# Battery.net
KiCad netlist of a schematic drawn in Altium Designer
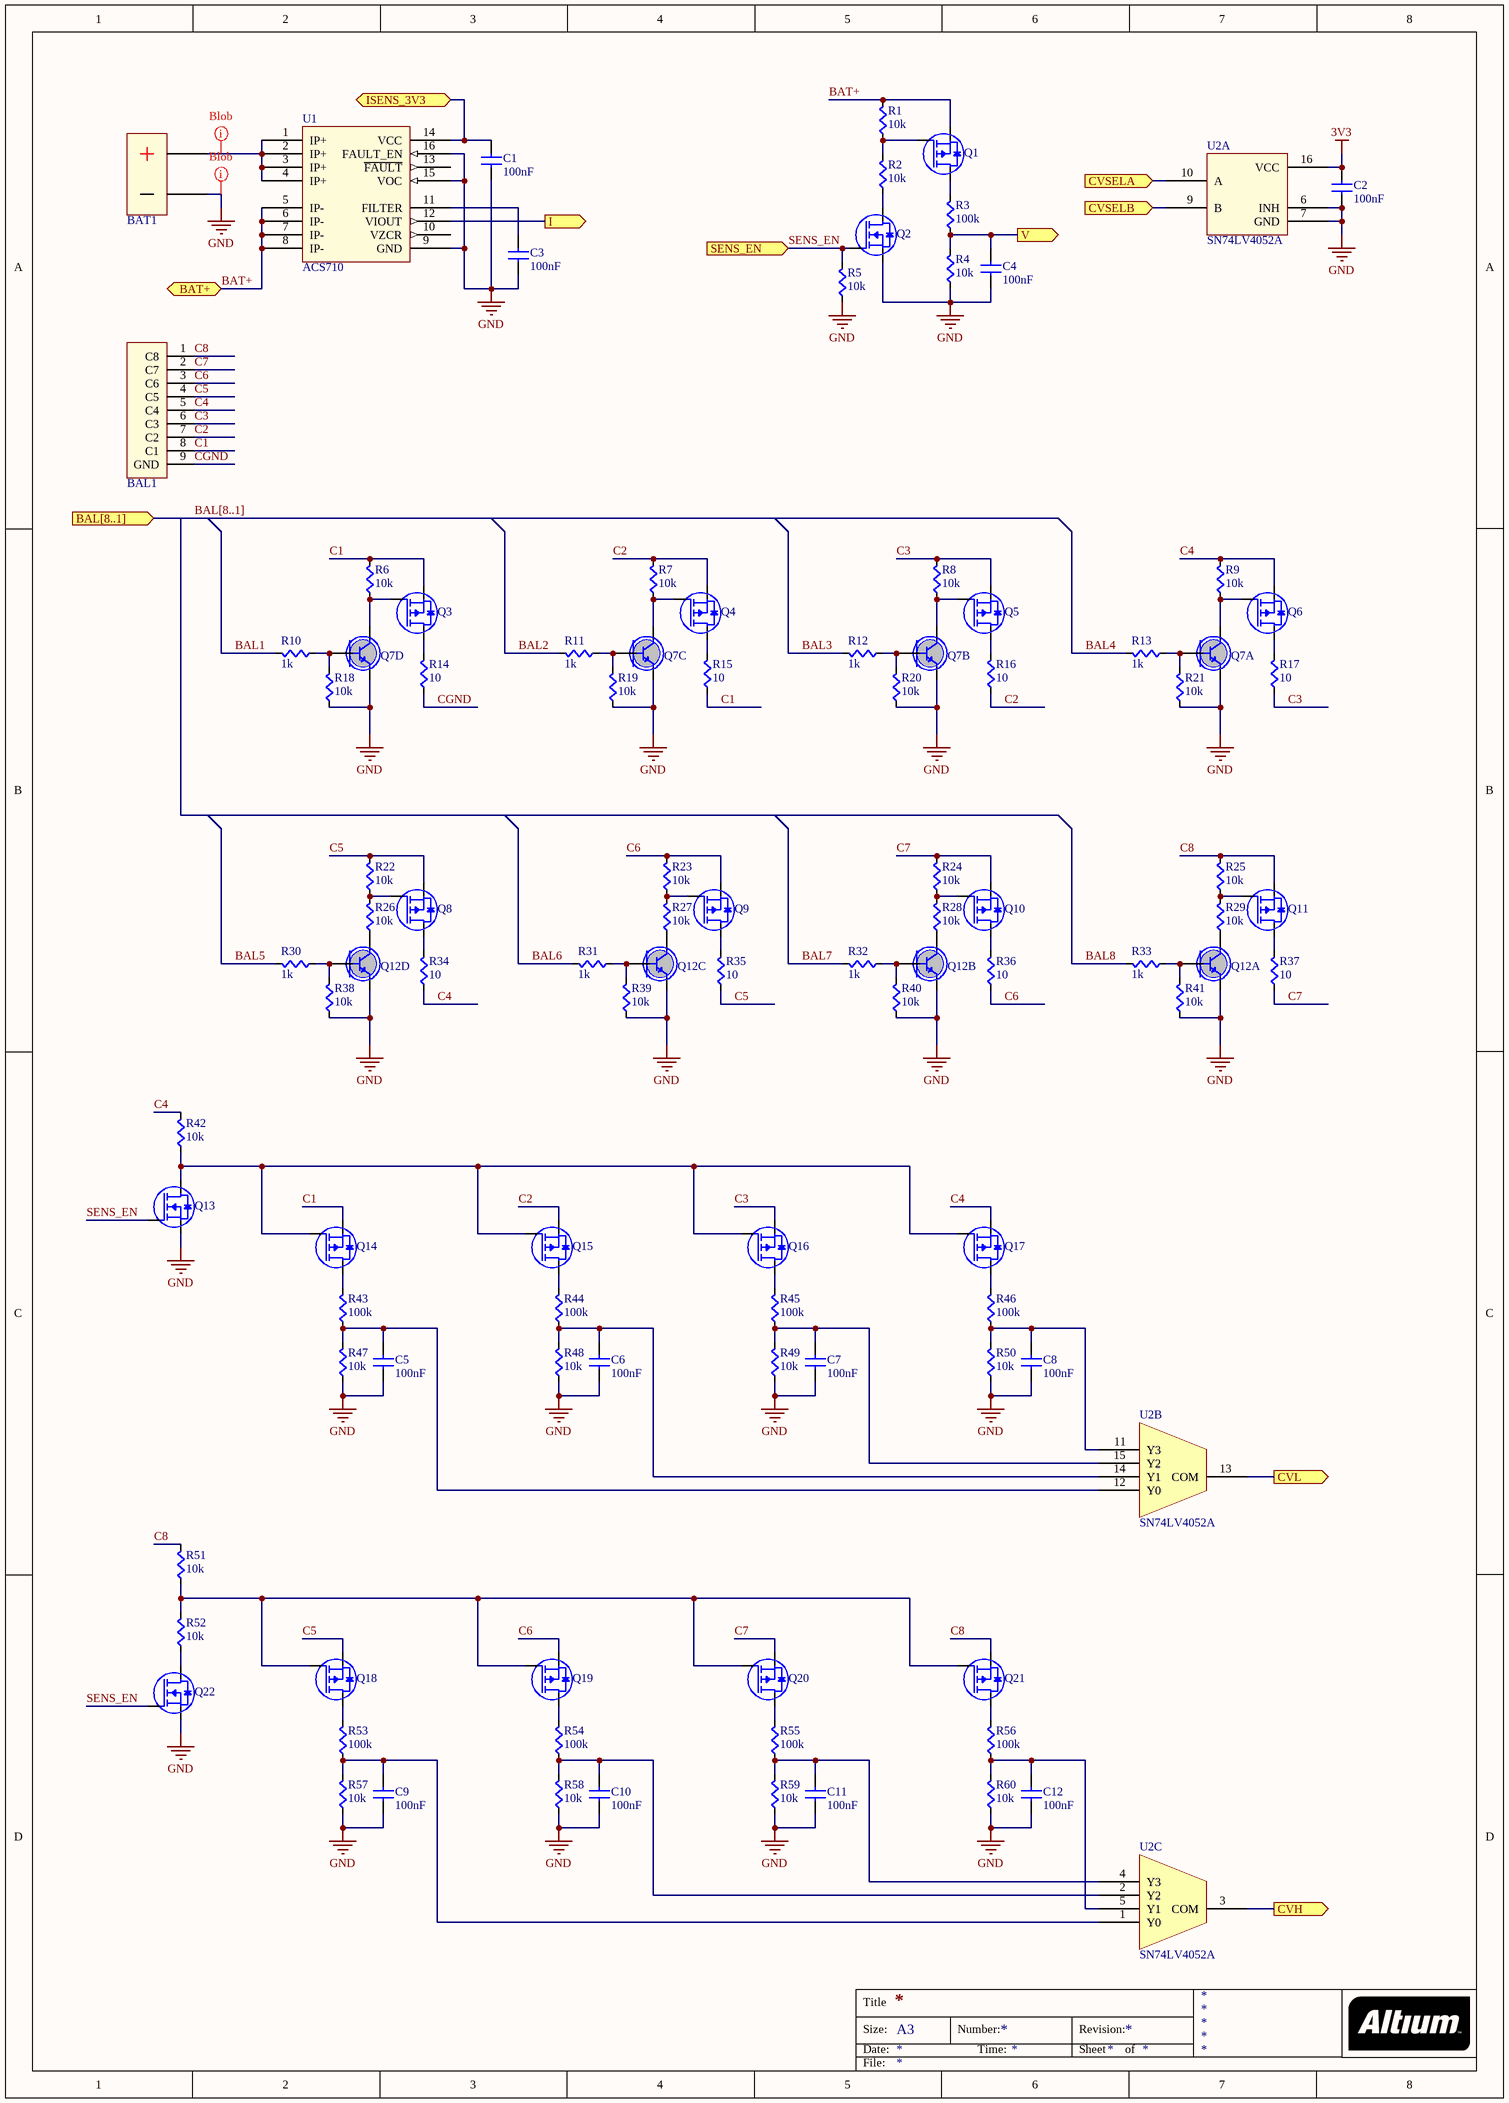
[diagram p0: Battery.SchDoc]

(export (version "E")
  (design (tool "Eeschema 10.0.6"))
  (components
    (comp (ref "BAL1") (value "JST1x9") (footprint "JST1x9") (libsource (lib "SubjuGator8") (part "JST1x9")))
    (comp (ref "BAT1")
      (value "BATWIRE")
      (footprint "BATWIRE12")
      (description "Two large gauge leads soldered directly to the board.")
      (libsource (lib "SubjuGator8") (part "BATWIRE"))
    )
    (comp (ref "C1")
      (value "100nF")
      (footprint "CAPC0603")
      (fields (field (name "Comment") "Cap"))
      (libsource (lib "SubjuGator8") (part "Cap"))
    )
    (comp (ref "C2")
      (value "100nF")
      (footprint "CAPC0603")
      (fields (field (name "Comment") "Cap"))
      (libsource (lib "SubjuGator8") (part "Cap"))
    )
    (comp (ref "C3")
      (value "100nF")
      (footprint "CAPC0603")
      (fields (field (name "Comment") "Cap"))
      (libsource (lib "SubjuGator8") (part "Cap"))
    )
    (comp (ref "C4")
      (value "100nF")
      (footprint "CAPC0603")
      (fields (field (name "Comment") "Cap"))
      (libsource (lib "SubjuGator8") (part "Cap"))
    )
    (comp (ref "C5")
      (value "100nF")
      (footprint "CAPC0603")
      (fields (field (name "Comment") "Cap"))
      (libsource (lib "SubjuGator8") (part "Cap"))
    )
    (comp (ref "C6")
      (value "100nF")
      (footprint "CAPC0603")
      (fields (field (name "Comment") "Cap"))
      (libsource (lib "SubjuGator8") (part "Cap"))
    )
    (comp (ref "C7")
      (value "100nF")
      (footprint "CAPC0603")
      (fields (field (name "Comment") "Cap"))
      (libsource (lib "SubjuGator8") (part "Cap"))
    )
    (comp (ref "C8")
      (value "100nF")
      (footprint "CAPC0603")
      (fields (field (name "Comment") "Cap"))
      (libsource (lib "SubjuGator8") (part "Cap"))
    )
    (comp (ref "C9")
      (value "100nF")
      (footprint "CAPC0603")
      (fields (field (name "Comment") "Cap"))
      (libsource (lib "SubjuGator8") (part "Cap"))
    )
    (comp (ref "C10")
      (value "100nF")
      (footprint "CAPC0603")
      (fields (field (name "Comment") "Cap"))
      (libsource (lib "SubjuGator8") (part "Cap"))
    )
    (comp (ref "C11")
      (value "100nF")
      (footprint "CAPC0603")
      (fields (field (name "Comment") "Cap"))
      (libsource (lib "SubjuGator8") (part "Cap"))
    )
    (comp (ref "C12")
      (value "100nF")
      (footprint "CAPC0603")
      (fields (field (name "Comment") "Cap"))
      (libsource (lib "SubjuGator8") (part "Cap"))
    )
    (comp (ref "Q1")
      (value "FDN5618P")
      (footprint "PowerSOT-3")
      (description "60V P-Channel Logic Level PowerTrench MOSFET")
      (libsource (lib "SubjuGator8") (part "FDN5618P"))
    )
    (comp (ref "Q2")
      (value "FDN5630")
      (footprint "PowerSOT-3")
      (description "60V N-Channel PowerTrench MOSFET")
      (libsource (lib "SubjuGator8") (part "FDN5630"))
    )
    (comp (ref "Q3")
      (value "FDN5618P")
      (footprint "PowerSOT-3")
      (description "60V P-Channel Logic Level PowerTrench MOSFET")
      (libsource (lib "SubjuGator8") (part "FDN5618P"))
    )
    (comp (ref "Q4")
      (value "FDN5618P")
      (footprint "PowerSOT-3")
      (description "60V P-Channel Logic Level PowerTrench MOSFET")
      (libsource (lib "SubjuGator8") (part "FDN5618P"))
    )
    (comp (ref "Q5")
      (value "FDN5618P")
      (footprint "PowerSOT-3")
      (description "60V P-Channel Logic Level PowerTrench MOSFET")
      (libsource (lib "SubjuGator8") (part "FDN5618P"))
    )
    (comp (ref "Q6")
      (value "FDN5618P")
      (footprint "PowerSOT-3")
      (description "60V P-Channel Logic Level PowerTrench MOSFET")
      (libsource (lib "SubjuGator8") (part "FDN5618P"))
    )
    (comp (ref "Q7")
      (value "MMPQ2222A")
      (footprint "MMPQ2222A")
      (description "Quad NPN General Purpose Amplifier")
      (libsource (lib "SubjuGator8") (part "MMPQ2222A"))
    )
    (comp (ref "Q8")
      (value "FDN5618P")
      (footprint "PowerSOT-3")
      (description "60V P-Channel Logic Level PowerTrench MOSFET")
      (libsource (lib "SubjuGator8") (part "FDN5618P"))
    )
    (comp (ref "Q9")
      (value "FDN5618P")
      (footprint "PowerSOT-3")
      (description "60V P-Channel Logic Level PowerTrench MOSFET")
      (libsource (lib "SubjuGator8") (part "FDN5618P"))
    )
    (comp (ref "Q10")
      (value "FDN5618P")
      (footprint "PowerSOT-3")
      (description "60V P-Channel Logic Level PowerTrench MOSFET")
      (libsource (lib "SubjuGator8") (part "FDN5618P"))
    )
    (comp (ref "Q11")
      (value "FDN5618P")
      (footprint "PowerSOT-3")
      (description "60V P-Channel Logic Level PowerTrench MOSFET")
      (libsource (lib "SubjuGator8") (part "FDN5618P"))
    )
    (comp (ref "Q12")
      (value "MMPQ2222A")
      (footprint "MMPQ2222A")
      (description "Quad NPN General Purpose Amplifier")
      (libsource (lib "SubjuGator8") (part "MMPQ2222A"))
    )
    (comp (ref "Q13")
      (value "FDN5630")
      (footprint "PowerSOT-3")
      (description "60V N-Channel PowerTrench MOSFET")
      (libsource (lib "SubjuGator8") (part "FDN5630"))
    )
    (comp (ref "Q14")
      (value "FDN5618P")
      (footprint "PowerSOT-3")
      (description "60V P-Channel Logic Level PowerTrench MOSFET")
      (libsource (lib "SubjuGator8") (part "FDN5618P"))
    )
    (comp (ref "Q15")
      (value "FDN5618P")
      (footprint "PowerSOT-3")
      (description "60V P-Channel Logic Level PowerTrench MOSFET")
      (libsource (lib "SubjuGator8") (part "FDN5618P"))
    )
    (comp (ref "Q16")
      (value "FDN5618P")
      (footprint "PowerSOT-3")
      (description "60V P-Channel Logic Level PowerTrench MOSFET")
      (libsource (lib "SubjuGator8") (part "FDN5618P"))
    )
    (comp (ref "Q17")
      (value "FDN5618P")
      (footprint "PowerSOT-3")
      (description "60V P-Channel Logic Level PowerTrench MOSFET")
      (libsource (lib "SubjuGator8") (part "FDN5618P"))
    )
    (comp (ref "Q18")
      (value "FDN5618P")
      (footprint "PowerSOT-3")
      (description "60V P-Channel Logic Level PowerTrench MOSFET")
      (libsource (lib "SubjuGator8") (part "FDN5618P"))
    )
    (comp (ref "Q19")
      (value "FDN5618P")
      (footprint "PowerSOT-3")
      (description "60V P-Channel Logic Level PowerTrench MOSFET")
      (libsource (lib "SubjuGator8") (part "FDN5618P"))
    )
    (comp (ref "Q20")
      (value "FDN5618P")
      (footprint "PowerSOT-3")
      (description "60V P-Channel Logic Level PowerTrench MOSFET")
      (libsource (lib "SubjuGator8") (part "FDN5618P"))
    )
    (comp (ref "Q21")
      (value "FDN5618P")
      (footprint "PowerSOT-3")
      (description "60V P-Channel Logic Level PowerTrench MOSFET")
      (libsource (lib "SubjuGator8") (part "FDN5618P"))
    )
    (comp (ref "Q22")
      (value "FDN5630")
      (footprint "PowerSOT-3")
      (description "60V N-Channel PowerTrench MOSFET")
      (libsource (lib "SubjuGator8") (part "FDN5630"))
    )
    (comp (ref "R1")
      (value "10k")
      (footprint "RES0603")
      (fields (field (name "Comment") "Res"))
      (libsource (lib "SubjuGator8") (part "Res"))
    )
    (comp (ref "R2")
      (value "10k")
      (footprint "RES0603")
      (fields (field (name "Comment") "Res"))
      (libsource (lib "SubjuGator8") (part "Res"))
    )
    (comp (ref "R3")
      (value "100k")
      (footprint "RES0603")
      (fields (field (name "Comment") "Res"))
      (libsource (lib "SubjuGator8") (part "Res"))
    )
    (comp (ref "R4")
      (value "10k")
      (footprint "RES0603")
      (fields (field (name "Comment") "Res"))
      (libsource (lib "SubjuGator8") (part "Res"))
    )
    (comp (ref "R5")
      (value "10k")
      (footprint "RES0603")
      (fields (field (name "Comment") "Res"))
      (libsource (lib "SubjuGator8") (part "Res"))
    )
    (comp (ref "R6")
      (value "10k")
      (footprint "RES0603")
      (fields (field (name "Comment") "Res"))
      (libsource (lib "SubjuGator8") (part "Res"))
    )
    (comp (ref "R7")
      (value "10k")
      (footprint "RES0603")
      (fields (field (name "Comment") "Res"))
      (libsource (lib "SubjuGator8") (part "Res"))
    )
    (comp (ref "R8")
      (value "10k")
      (footprint "RES0603")
      (fields (field (name "Comment") "Res"))
      (libsource (lib "SubjuGator8") (part "Res"))
    )
    (comp (ref "R9")
      (value "10k")
      (footprint "RES0603")
      (fields (field (name "Comment") "Res"))
      (libsource (lib "SubjuGator8") (part "Res"))
    )
    (comp (ref "R10")
      (value "1k")
      (footprint "RES0603")
      (fields (field (name "Comment") "Res"))
      (libsource (lib "SubjuGator8") (part "Res"))
    )
    (comp (ref "R11")
      (value "1k")
      (footprint "RES0603")
      (fields (field (name "Comment") "Res"))
      (libsource (lib "SubjuGator8") (part "Res"))
    )
    (comp (ref "R12")
      (value "1k")
      (footprint "RES0603")
      (fields (field (name "Comment") "Res"))
      (libsource (lib "SubjuGator8") (part "Res"))
    )
    (comp (ref "R13")
      (value "1k")
      (footprint "RES0603")
      (fields (field (name "Comment") "Res"))
      (libsource (lib "SubjuGator8") (part "Res"))
    )
    (comp (ref "R14")
      (value "10")
      (footprint "FMP200")
      (fields (field (name "Comment") "Res"))
      (libsource (lib "SubjuGator8") (part "Res"))
    )
    (comp (ref "R15")
      (value "10")
      (footprint "FMP200")
      (fields (field (name "Comment") "Res"))
      (libsource (lib "SubjuGator8") (part "Res"))
    )
    (comp (ref "R16")
      (value "10")
      (footprint "FMP200")
      (fields (field (name "Comment") "Res"))
      (libsource (lib "SubjuGator8") (part "Res"))
    )
    (comp (ref "R17")
      (value "10")
      (footprint "FMP200")
      (fields (field (name "Comment") "Res"))
      (libsource (lib "SubjuGator8") (part "Res"))
    )
    (comp (ref "R18")
      (value "10k")
      (footprint "RES0603")
      (fields (field (name "Comment") "Res"))
      (libsource (lib "SubjuGator8") (part "Res"))
    )
    (comp (ref "R19")
      (value "10k")
      (footprint "RES0603")
      (fields (field (name "Comment") "Res"))
      (libsource (lib "SubjuGator8") (part "Res"))
    )
    (comp (ref "R20")
      (value "10k")
      (footprint "RES0603")
      (fields (field (name "Comment") "Res"))
      (libsource (lib "SubjuGator8") (part "Res"))
    )
    (comp (ref "R21")
      (value "10k")
      (footprint "RES0603")
      (fields (field (name "Comment") "Res"))
      (libsource (lib "SubjuGator8") (part "Res"))
    )
    (comp (ref "R22")
      (value "10k")
      (footprint "RES0603")
      (fields (field (name "Comment") "Res"))
      (libsource (lib "SubjuGator8") (part "Res"))
    )
    (comp (ref "R23")
      (value "10k")
      (footprint "RES0603")
      (fields (field (name "Comment") "Res"))
      (libsource (lib "SubjuGator8") (part "Res"))
    )
    (comp (ref "R24")
      (value "10k")
      (footprint "RES0603")
      (fields (field (name "Comment") "Res"))
      (libsource (lib "SubjuGator8") (part "Res"))
    )
    (comp (ref "R25")
      (value "10k")
      (footprint "RES0603")
      (fields (field (name "Comment") "Res"))
      (libsource (lib "SubjuGator8") (part "Res"))
    )
    (comp (ref "R26")
      (value "10k")
      (footprint "RES0603")
      (fields (field (name "Comment") "Res"))
      (libsource (lib "SubjuGator8") (part "Res"))
    )
    (comp (ref "R27")
      (value "10k")
      (footprint "RES0603")
      (fields (field (name "Comment") "Res"))
      (libsource (lib "SubjuGator8") (part "Res"))
    )
    (comp (ref "R28")
      (value "10k")
      (footprint "RES0603")
      (fields (field (name "Comment") "Res"))
      (libsource (lib "SubjuGator8") (part "Res"))
    )
    (comp (ref "R29")
      (value "10k")
      (footprint "RES0603")
      (fields (field (name "Comment") "Res"))
      (libsource (lib "SubjuGator8") (part "Res"))
    )
    (comp (ref "R30")
      (value "1k")
      (footprint "RES0603")
      (fields (field (name "Comment") "Res"))
      (libsource (lib "SubjuGator8") (part "Res"))
    )
    (comp (ref "R31")
      (value "1k")
      (footprint "RES0603")
      (fields (field (name "Comment") "Res"))
      (libsource (lib "SubjuGator8") (part "Res"))
    )
    (comp (ref "R32")
      (value "1k")
      (footprint "RES0603")
      (fields (field (name "Comment") "Res"))
      (libsource (lib "SubjuGator8") (part "Res"))
    )
    (comp (ref "R33")
      (value "1k")
      (footprint "RES0603")
      (fields (field (name "Comment") "Res"))
      (libsource (lib "SubjuGator8") (part "Res"))
    )
    (comp (ref "R34")
      (value "10")
      (footprint "FMP200")
      (fields (field (name "Comment") "Res"))
      (libsource (lib "SubjuGator8") (part "Res"))
    )
    (comp (ref "R35")
      (value "10")
      (footprint "FMP200")
      (fields (field (name "Comment") "Res"))
      (libsource (lib "SubjuGator8") (part "Res"))
    )
    (comp (ref "R36")
      (value "10")
      (footprint "FMP200")
      (fields (field (name "Comment") "Res"))
      (libsource (lib "SubjuGator8") (part "Res"))
    )
    (comp (ref "R37")
      (value "10")
      (footprint "FMP200")
      (fields (field (name "Comment") "Res"))
      (libsource (lib "SubjuGator8") (part "Res"))
    )
    (comp (ref "R38")
      (value "10k")
      (footprint "RES0603")
      (fields (field (name "Comment") "Res"))
      (libsource (lib "SubjuGator8") (part "Res"))
    )
    (comp (ref "R39")
      (value "10k")
      (footprint "RES0603")
      (fields (field (name "Comment") "Res"))
      (libsource (lib "SubjuGator8") (part "Res"))
    )
    (comp (ref "R40")
      (value "10k")
      (footprint "RES0603")
      (fields (field (name "Comment") "Res"))
      (libsource (lib "SubjuGator8") (part "Res"))
    )
    (comp (ref "R41")
      (value "10k")
      (footprint "RES0603")
      (fields (field (name "Comment") "Res"))
      (libsource (lib "SubjuGator8") (part "Res"))
    )
    (comp (ref "R42")
      (value "10k")
      (footprint "RES0603")
      (fields (field (name "Comment") "Res"))
      (libsource (lib "SubjuGator8") (part "Res"))
    )
    (comp (ref "R43")
      (value "100k")
      (footprint "RES0603")
      (fields (field (name "Comment") "Res"))
      (libsource (lib "SubjuGator8") (part "Res"))
    )
    (comp (ref "R44")
      (value "100k")
      (footprint "RES0603")
      (fields (field (name "Comment") "Res"))
      (libsource (lib "SubjuGator8") (part "Res"))
    )
    (comp (ref "R45")
      (value "100k")
      (footprint "RES0603")
      (fields (field (name "Comment") "Res"))
      (libsource (lib "SubjuGator8") (part "Res"))
    )
    (comp (ref "R46")
      (value "100k")
      (footprint "RES0603")
      (fields (field (name "Comment") "Res"))
      (libsource (lib "SubjuGator8") (part "Res"))
    )
    (comp (ref "R47")
      (value "10k")
      (footprint "RES0603")
      (fields (field (name "Comment") "Res"))
      (libsource (lib "SubjuGator8") (part "Res"))
    )
    (comp (ref "R48")
      (value "10k")
      (footprint "RES0603")
      (fields (field (name "Comment") "Res"))
      (libsource (lib "SubjuGator8") (part "Res"))
    )
    (comp (ref "R49")
      (value "10k")
      (footprint "RES0603")
      (fields (field (name "Comment") "Res"))
      (libsource (lib "SubjuGator8") (part "Res"))
    )
    (comp (ref "R50")
      (value "10k")
      (footprint "RES0603")
      (fields (field (name "Comment") "Res"))
      (libsource (lib "SubjuGator8") (part "Res"))
    )
    (comp (ref "R51")
      (value "10k")
      (footprint "RES0603")
      (fields (field (name "Comment") "Res"))
      (libsource (lib "SubjuGator8") (part "Res"))
    )
    (comp (ref "R52")
      (value "10k")
      (footprint "RES0603")
      (fields (field (name "Comment") "Res"))
      (libsource (lib "SubjuGator8") (part "Res"))
    )
    (comp (ref "R53")
      (value "100k")
      (footprint "RES0603")
      (fields (field (name "Comment") "Res"))
      (libsource (lib "SubjuGator8") (part "Res"))
    )
    (comp (ref "R54")
      (value "100k")
      (footprint "RES0603")
      (fields (field (name "Comment") "Res"))
      (libsource (lib "SubjuGator8") (part "Res"))
    )
    (comp (ref "R55")
      (value "100k")
      (footprint "RES0603")
      (fields (field (name "Comment") "Res"))
      (libsource (lib "SubjuGator8") (part "Res"))
    )
    (comp (ref "R56")
      (value "100k")
      (footprint "RES0603")
      (fields (field (name "Comment") "Res"))
      (libsource (lib "SubjuGator8") (part "Res"))
    )
    (comp (ref "R57")
      (value "10k")
      (footprint "RES0603")
      (fields (field (name "Comment") "Res"))
      (libsource (lib "SubjuGator8") (part "Res"))
    )
    (comp (ref "R58")
      (value "10k")
      (footprint "RES0603")
      (fields (field (name "Comment") "Res"))
      (libsource (lib "SubjuGator8") (part "Res"))
    )
    (comp (ref "R59")
      (value "10k")
      (footprint "RES0603")
      (fields (field (name "Comment") "Res"))
      (libsource (lib "SubjuGator8") (part "Res"))
    )
    (comp (ref "R60")
      (value "10k")
      (footprint "RES0603")
      (fields (field (name "Comment") "Res"))
      (libsource (lib "SubjuGator8") (part "Res"))
    )
    (comp (ref "U1")
      (value "ACS710")
      (footprint "ACS710_NOPIN")
      (description "Current Sensor with Integrated Overcurrent Detection")
      (libsource (lib "SubjuGator8") (part "ACS710"))
    )
    (comp (ref "U2")
      (value "SN74LV4052A")
      (footprint "SN74LV4052AD")
      (description "Dual 4-Channel Analog Multiplexers/Demultiplexers")
      (libsource (lib "SubjuGator8") (part "SN74LV4052A"))
    )
  )
  (nets
    (net (code "1") (name "/BAL1") (class "Default")
      (node (ref "R10") (pin "1") (pinfunction "A_1") (pintype "passive"))
    )
    (net (code "2") (name "/BAL2") (class "Default")
      (node (ref "R11") (pin "1") (pinfunction "A_1") (pintype "passive"))
    )
    (net (code "3") (name "/BAL3") (class "Default")
      (node (ref "R12") (pin "1") (pinfunction "A_1") (pintype "passive"))
    )
    (net (code "4") (name "/BAL4") (class "Default")
      (node (ref "R13") (pin "1") (pinfunction "A_1") (pintype "passive"))
    )
    (net (code "5") (name "/BAL5") (class "Default")
      (node (ref "R30") (pin "1") (pinfunction "A_1") (pintype "passive"))
    )
    (net (code "6") (name "/BAL6") (class "Default")
      (node (ref "R31") (pin "1") (pinfunction "A_1") (pintype "passive"))
    )
    (net (code "7") (name "/BAL7") (class "Default")
      (node (ref "R32") (pin "1") (pinfunction "A_1") (pintype "passive"))
    )
    (net (code "8") (name "/BAL8") (class "Default")
      (node (ref "R33") (pin "1") (pinfunction "A_1") (pintype "passive"))
    )
    (net (code "10") (name "/BAT+") (class "Default")
      (node (ref "Q1") (pin "S") (pinfunction "S_S") (pintype "passive"))
      (node (ref "R1") (pin "1") (pinfunction "A_1") (pintype "passive"))
      (node (ref "U1") (pin "5") (pinfunction "IP-_5") (pintype "passive"))
      (node (ref "U1") (pin "6") (pinfunction "IP-_6") (pintype "passive"))
      (node (ref "U1") (pin "7") (pinfunction "IP-_7") (pintype "passive"))
      (node (ref "U1") (pin "8") (pinfunction "IP-_8") (pintype "passive"))
    )
    (net (code "11") (name "/C1") (class "Default")
      (node (ref "BAL1") (pin "8") (pinfunction "C1_8") (pintype "passive"))
      (node (ref "Q14") (pin "S") (pinfunction "S_S") (pintype "passive"))
      (node (ref "Q3") (pin "S") (pinfunction "S_S") (pintype "passive"))
      (node (ref "R15") (pin "2") (pinfunction "B_2") (pintype "passive"))
      (node (ref "R6") (pin "1") (pinfunction "A_1") (pintype "passive"))
    )
    (net (code "12") (name "/C2") (class "Default")
      (node (ref "BAL1") (pin "7") (pinfunction "C2_7") (pintype "passive"))
      (node (ref "Q15") (pin "S") (pinfunction "S_S") (pintype "passive"))
      (node (ref "Q4") (pin "S") (pinfunction "S_S") (pintype "passive"))
      (node (ref "R16") (pin "2") (pinfunction "B_2") (pintype "passive"))
      (node (ref "R7") (pin "1") (pinfunction "A_1") (pintype "passive"))
    )
    (net (code "13") (name "/C3") (class "Default")
      (node (ref "BAL1") (pin "6") (pinfunction "C3_6") (pintype "passive"))
      (node (ref "Q16") (pin "S") (pinfunction "S_S") (pintype "passive"))
      (node (ref "Q5") (pin "S") (pinfunction "S_S") (pintype "passive"))
      (node (ref "R17") (pin "2") (pinfunction "B_2") (pintype "passive"))
      (node (ref "R8") (pin "1") (pinfunction "A_1") (pintype "passive"))
    )
    (net (code "14") (name "/C4") (class "Default")
      (node (ref "BAL1") (pin "5") (pinfunction "C4_5") (pintype "passive"))
      (node (ref "Q17") (pin "S") (pinfunction "S_S") (pintype "passive"))
      (node (ref "Q6") (pin "S") (pinfunction "S_S") (pintype "passive"))
      (node (ref "R34") (pin "2") (pinfunction "B_2") (pintype "passive"))
      (node (ref "R42") (pin "1") (pinfunction "A_1") (pintype "passive"))
      (node (ref "R9") (pin "1") (pinfunction "A_1") (pintype "passive"))
    )
    (net (code "15") (name "/C5") (class "Default")
      (node (ref "BAL1") (pin "4") (pinfunction "C5_4") (pintype "passive"))
      (node (ref "Q18") (pin "S") (pinfunction "S_S") (pintype "passive"))
      (node (ref "Q8") (pin "S") (pinfunction "S_S") (pintype "passive"))
      (node (ref "R22") (pin "1") (pinfunction "A_1") (pintype "passive"))
      (node (ref "R35") (pin "2") (pinfunction "B_2") (pintype "passive"))
    )
    (net (code "16") (name "/C6") (class "Default")
      (node (ref "BAL1") (pin "3") (pinfunction "C6_3") (pintype "passive"))
      (node (ref "Q19") (pin "S") (pinfunction "S_S") (pintype "passive"))
      (node (ref "Q9") (pin "S") (pinfunction "S_S") (pintype "passive"))
      (node (ref "R23") (pin "1") (pinfunction "A_1") (pintype "passive"))
      (node (ref "R36") (pin "2") (pinfunction "B_2") (pintype "passive"))
    )
    (net (code "17") (name "/C7") (class "Default")
      (node (ref "BAL1") (pin "2") (pinfunction "C7_2") (pintype "passive"))
      (node (ref "Q10") (pin "S") (pinfunction "S_S") (pintype "passive"))
      (node (ref "Q20") (pin "S") (pinfunction "S_S") (pintype "passive"))
      (node (ref "R24") (pin "1") (pinfunction "A_1") (pintype "passive"))
      (node (ref "R37") (pin "2") (pinfunction "B_2") (pintype "passive"))
    )
    (net (code "18") (name "/C8") (class "Default")
      (node (ref "BAL1") (pin "1") (pinfunction "C8_1") (pintype "passive"))
      (node (ref "Q11") (pin "S") (pinfunction "S_S") (pintype "passive"))
      (node (ref "Q21") (pin "S") (pinfunction "S_S") (pintype "passive"))
      (node (ref "R25") (pin "1") (pinfunction "A_1") (pintype "passive"))
      (node (ref "R51") (pin "1") (pinfunction "A_1") (pintype "passive"))
    )
    (net (code "19") (name "/CGND") (class "Default")
      (node (ref "BAL1") (pin "9") (pinfunction "GND_9") (pintype "passive"))
      (node (ref "R14") (pin "2") (pinfunction "B_2") (pintype "passive"))
    )
    (net (code "20") (name "/CVH") (class "Default")
      (node (ref "U2") (pin "3") (pinfunction "COM_3") (pintype "passive"))
    )
    (net (code "21") (name "/CVL") (class "Default")
      (node (ref "U2") (pin "13") (pinfunction "COM_13") (pintype "passive"))
    )
    (net (code "22") (name "/CVSELA") (class "Default")
      (node (ref "U2") (pin "10") (pinfunction "A_10") (pintype "passive"))
    )
    (net (code "23") (name "/CVSELB") (class "Default")
      (node (ref "U2") (pin "9") (pinfunction "B_9") (pintype "passive"))
    )
    (net (code "24") (name "/I") (class "Default")
      (node (ref "U1") (pin "12") (pinfunction "VIOUT_12") (pintype "output"))
    )
    (net (code "25") (name "/ISENS_3V3") (class "Default")
      (node (ref "C1") (pin "1") (pinfunction "A_1") (pintype "passive"))
      (node (ref "U1") (pin "14") (pinfunction "VCC_14") (pintype "power_in"))
    )
    (net (code "26") (name "/SENS_EN") (class "Default")
      (node (ref "Q13") (pin "G") (pinfunction "G_G") (pintype "passive"))
      (node (ref "Q2") (pin "G") (pinfunction "G_G") (pintype "passive"))
      (node (ref "Q22") (pin "G") (pinfunction "G_G") (pintype "passive"))
      (node (ref "R5") (pin "1") (pinfunction "A_1") (pintype "passive"))
    )
    (net (code "27") (name "/V") (class "Default")
      (node (ref "C4") (pin "1") (pinfunction "A_1") (pintype "passive"))
      (node (ref "R3") (pin "2") (pinfunction "B_2") (pintype "passive"))
      (node (ref "R4") (pin "1") (pinfunction "A_1") (pintype "passive"))
    )
    (net (code "28") (name "3V3") (class "Default")
      (node (ref "C2") (pin "1") (pinfunction "A_1") (pintype "passive"))
      (node (ref "U2") (pin "16") (pinfunction "VCC_16") (pintype "power_in"))
    )
    (net (code "29") (name "GND") (class "Default")
      (node (ref "BAT1") (pin "-") (pinfunction "-_-") (pintype "power_in"))
      (node (ref "C1") (pin "2") (pinfunction "B_2") (pintype "passive"))
      (node (ref "C10") (pin "2") (pinfunction "B_2") (pintype "passive"))
      (node (ref "C11") (pin "2") (pinfunction "B_2") (pintype "passive"))
      (node (ref "C12") (pin "2") (pinfunction "B_2") (pintype "passive"))
      (node (ref "C2") (pin "2") (pinfunction "B_2") (pintype "passive"))
      (node (ref "C3") (pin "2") (pinfunction "B_2") (pintype "passive"))
      (node (ref "C4") (pin "2") (pinfunction "B_2") (pintype "passive"))
      (node (ref "C5") (pin "2") (pinfunction "B_2") (pintype "passive"))
      (node (ref "C6") (pin "2") (pinfunction "B_2") (pintype "passive"))
      (node (ref "C7") (pin "2") (pinfunction "B_2") (pintype "passive"))
      (node (ref "C8") (pin "2") (pinfunction "B_2") (pintype "passive"))
      (node (ref "C9") (pin "2") (pinfunction "B_2") (pintype "passive"))
      (node (ref "Q12") (pin "10") (pinfunction "E4_10") (pintype "passive"))
      (node (ref "Q12") (pin "12") (pinfunction "E3_12") (pintype "passive"))
      (node (ref "Q12") (pin "14") (pinfunction "E2_14") (pintype "passive"))
      (node (ref "Q12") (pin "16") (pinfunction "E1_16") (pintype "passive"))
      (node (ref "Q13") (pin "S") (pinfunction "S_S") (pintype "passive"))
      (node (ref "Q2") (pin "S") (pinfunction "S_S") (pintype "passive"))
      (node (ref "Q22") (pin "S") (pinfunction "S_S") (pintype "passive"))
      (node (ref "Q7") (pin "10") (pinfunction "E4_10") (pintype "passive"))
      (node (ref "Q7") (pin "12") (pinfunction "E3_12") (pintype "passive"))
      (node (ref "Q7") (pin "14") (pinfunction "E2_14") (pintype "passive"))
      (node (ref "Q7") (pin "16") (pinfunction "E1_16") (pintype "passive"))
      (node (ref "R18") (pin "2") (pinfunction "B_2") (pintype "passive"))
      (node (ref "R19") (pin "2") (pinfunction "B_2") (pintype "passive"))
      (node (ref "R20") (pin "2") (pinfunction "B_2") (pintype "passive"))
      (node (ref "R21") (pin "2") (pinfunction "B_2") (pintype "passive"))
      (node (ref "R38") (pin "2") (pinfunction "B_2") (pintype "passive"))
      (node (ref "R39") (pin "2") (pinfunction "B_2") (pintype "passive"))
      (node (ref "R4") (pin "2") (pinfunction "B_2") (pintype "passive"))
      (node (ref "R40") (pin "2") (pinfunction "B_2") (pintype "passive"))
      (node (ref "R41") (pin "2") (pinfunction "B_2") (pintype "passive"))
      (node (ref "R47") (pin "2") (pinfunction "B_2") (pintype "passive"))
      (node (ref "R48") (pin "2") (pinfunction "B_2") (pintype "passive"))
      (node (ref "R49") (pin "2") (pinfunction "B_2") (pintype "passive"))
      (node (ref "R5") (pin "2") (pinfunction "B_2") (pintype "passive"))
      (node (ref "R50") (pin "2") (pinfunction "B_2") (pintype "passive"))
      (node (ref "R57") (pin "2") (pinfunction "B_2") (pintype "passive"))
      (node (ref "R58") (pin "2") (pinfunction "B_2") (pintype "passive"))
      (node (ref "R59") (pin "2") (pinfunction "B_2") (pintype "passive"))
      (node (ref "R60") (pin "2") (pinfunction "B_2") (pintype "passive"))
      (node (ref "U1") (pin "15") (pinfunction "VOC_15") (pintype "input"))
      (node (ref "U1") (pin "16") (pinfunction "FAULT_EN_16") (pintype "input"))
      (node (ref "U1") (pin "9") (pinfunction "GND_9") (pintype "power_in"))
      (node (ref "U2") (pin "6") (pinfunction "INH_6") (pintype "passive"))
      (node (ref "U2") (pin "7") (pinfunction "GND_7") (pintype "passive"))
    )
    (net (code "30") (name "Net-(BAT1-Pad+)") (class "Default")
      (node (ref "BAT1") (pin "+") (pinfunction "+_+") (pintype "power_in"))
      (node (ref "U1") (pin "1") (pinfunction "IP+_1") (pintype "passive"))
      (node (ref "U1") (pin "2") (pinfunction "IP+_2") (pintype "passive"))
      (node (ref "U1") (pin "3") (pinfunction "IP+_3") (pintype "passive"))
      (node (ref "U1") (pin "4") (pinfunction "IP+_4") (pintype "passive"))
    )
    (net (code "31") (name "Net-(C3-A)") (class "Default")
      (node (ref "C3") (pin "1") (pinfunction "A_1") (pintype "passive"))
      (node (ref "U1") (pin "11") (pinfunction "FILTER_11") (pintype "passive"))
    )
    (net (code "32") (name "Net-(C5-A)") (class "Default")
      (node (ref "C5") (pin "1") (pinfunction "A_1") (pintype "passive"))
      (node (ref "R43") (pin "2") (pinfunction "B_2") (pintype "passive"))
      (node (ref "R47") (pin "1") (pinfunction "A_1") (pintype "passive"))
      (node (ref "U2") (pin "12") (pinfunction "Y0_12") (pintype "passive"))
    )
    (net (code "33") (name "Net-(C6-A)") (class "Default")
      (node (ref "C6") (pin "1") (pinfunction "A_1") (pintype "passive"))
      (node (ref "R44") (pin "2") (pinfunction "B_2") (pintype "passive"))
      (node (ref "R48") (pin "1") (pinfunction "A_1") (pintype "passive"))
      (node (ref "U2") (pin "14") (pinfunction "Y1_14") (pintype "passive"))
    )
    (net (code "34") (name "Net-(C7-A)") (class "Default")
      (node (ref "C7") (pin "1") (pinfunction "A_1") (pintype "passive"))
      (node (ref "R45") (pin "2") (pinfunction "B_2") (pintype "passive"))
      (node (ref "R49") (pin "1") (pinfunction "A_1") (pintype "passive"))
      (node (ref "U2") (pin "15") (pinfunction "Y2_15") (pintype "passive"))
    )
    (net (code "35") (name "Net-(C8-A)") (class "Default")
      (node (ref "C8") (pin "1") (pinfunction "A_1") (pintype "passive"))
      (node (ref "R46") (pin "2") (pinfunction "B_2") (pintype "passive"))
      (node (ref "R50") (pin "1") (pinfunction "A_1") (pintype "passive"))
      (node (ref "U2") (pin "11") (pinfunction "Y3_11") (pintype "passive"))
    )
    (net (code "36") (name "Net-(C9-A)") (class "Default")
      (node (ref "C9") (pin "1") (pinfunction "A_1") (pintype "passive"))
      (node (ref "R53") (pin "2") (pinfunction "B_2") (pintype "passive"))
      (node (ref "R57") (pin "1") (pinfunction "A_1") (pintype "passive"))
      (node (ref "U2") (pin "1") (pinfunction "Y0_1") (pintype "passive"))
    )
    (net (code "37") (name "Net-(C10-A)") (class "Default")
      (node (ref "C10") (pin "1") (pinfunction "A_1") (pintype "passive"))
      (node (ref "R54") (pin "2") (pinfunction "B_2") (pintype "passive"))
      (node (ref "R58") (pin "1") (pinfunction "A_1") (pintype "passive"))
      (node (ref "U2") (pin "2") (pinfunction "Y2_2") (pintype "passive"))
    )
    (net (code "38") (name "Net-(C11-A)") (class "Default")
      (node (ref "C11") (pin "1") (pinfunction "A_1") (pintype "passive"))
      (node (ref "R55") (pin "2") (pinfunction "B_2") (pintype "passive"))
      (node (ref "R59") (pin "1") (pinfunction "A_1") (pintype "passive"))
      (node (ref "U2") (pin "4") (pinfunction "Y3_4") (pintype "passive"))
    )
    (net (code "39") (name "Net-(C12-A)") (class "Default")
      (node (ref "C12") (pin "1") (pinfunction "A_1") (pintype "passive"))
      (node (ref "R56") (pin "2") (pinfunction "B_2") (pintype "passive"))
      (node (ref "R60") (pin "1") (pinfunction "A_1") (pintype "passive"))
      (node (ref "U2") (pin "5") (pinfunction "Y1_5") (pintype "passive"))
    )
    (net (code "40") (name "Net-(Q7A-B1)") (class "Default")
      (node (ref "Q7") (pin "15") (pinfunction "B1_15") (pintype "passive"))
      (node (ref "R13") (pin "2") (pinfunction "B_2") (pintype "passive"))
      (node (ref "R21") (pin "1") (pinfunction "A_1") (pintype "passive"))
    )
    (net (code "41") (name "Net-(Q7A-C1)") (class "Default")
      (node (ref "Q6") (pin "G") (pinfunction "G_G") (pintype "passive"))
      (node (ref "Q7") (pin "1") (pinfunction "C1_1") (pintype "passive"))
      (node (ref "R9") (pin "2") (pinfunction "B_2") (pintype "passive"))
    )
    (net (code "42") (name "Net-(Q7B-B2)") (class "Default")
      (node (ref "Q7") (pin "13") (pinfunction "B2_13") (pintype "passive"))
      (node (ref "R12") (pin "2") (pinfunction "B_2") (pintype "passive"))
      (node (ref "R20") (pin "1") (pinfunction "A_1") (pintype "passive"))
    )
    (net (code "43") (name "Net-(Q7B-C2)") (class "Default")
      (node (ref "Q5") (pin "G") (pinfunction "G_G") (pintype "passive"))
      (node (ref "Q7") (pin "3") (pinfunction "C2_3") (pintype "passive"))
      (node (ref "R8") (pin "2") (pinfunction "B_2") (pintype "passive"))
    )
    (net (code "44") (name "Net-(Q7C-B3)") (class "Default")
      (node (ref "Q7") (pin "11") (pinfunction "B3_11") (pintype "passive"))
      (node (ref "R11") (pin "2") (pinfunction "B_2") (pintype "passive"))
      (node (ref "R19") (pin "1") (pinfunction "A_1") (pintype "passive"))
    )
    (net (code "45") (name "Net-(Q7C-C3)") (class "Default")
      (node (ref "Q4") (pin "G") (pinfunction "G_G") (pintype "passive"))
      (node (ref "Q7") (pin "5") (pinfunction "C3_5") (pintype "passive"))
      (node (ref "R7") (pin "2") (pinfunction "B_2") (pintype "passive"))
    )
    (net (code "46") (name "Net-(Q7D-B4)") (class "Default")
      (node (ref "Q7") (pin "9") (pinfunction "B4_9") (pintype "passive"))
      (node (ref "R10") (pin "2") (pinfunction "B_2") (pintype "passive"))
      (node (ref "R18") (pin "1") (pinfunction "A_1") (pintype "passive"))
    )
    (net (code "47") (name "Net-(Q7D-C4)") (class "Default")
      (node (ref "Q3") (pin "G") (pinfunction "G_G") (pintype "passive"))
      (node (ref "Q7") (pin "7") (pinfunction "C4_7") (pintype "passive"))
      (node (ref "R6") (pin "2") (pinfunction "B_2") (pintype "passive"))
    )
    (net (code "48") (name "Net-(Q12A-B1)") (class "Default")
      (node (ref "Q12") (pin "15") (pinfunction "B1_15") (pintype "passive"))
      (node (ref "R33") (pin "2") (pinfunction "B_2") (pintype "passive"))
      (node (ref "R41") (pin "1") (pinfunction "A_1") (pintype "passive"))
    )
    (net (code "49") (name "Net-(Q12A-C1)") (class "Default")
      (node (ref "Q12") (pin "1") (pinfunction "C1_1") (pintype "passive"))
      (node (ref "R29") (pin "2") (pinfunction "B_2") (pintype "passive"))
    )
    (net (code "50") (name "Net-(Q12B-B2)") (class "Default")
      (node (ref "Q12") (pin "13") (pinfunction "B2_13") (pintype "passive"))
      (node (ref "R32") (pin "2") (pinfunction "B_2") (pintype "passive"))
      (node (ref "R40") (pin "1") (pinfunction "A_1") (pintype "passive"))
    )
    (net (code "51") (name "Net-(Q12B-C2)") (class "Default")
      (node (ref "Q12") (pin "3") (pinfunction "C2_3") (pintype "passive"))
      (node (ref "R28") (pin "2") (pinfunction "B_2") (pintype "passive"))
    )
    (net (code "52") (name "Net-(Q12C-B3)") (class "Default")
      (node (ref "Q12") (pin "11") (pinfunction "B3_11") (pintype "passive"))
      (node (ref "R31") (pin "2") (pinfunction "B_2") (pintype "passive"))
      (node (ref "R39") (pin "1") (pinfunction "A_1") (pintype "passive"))
    )
    (net (code "53") (name "Net-(Q12C-C3)") (class "Default")
      (node (ref "Q12") (pin "5") (pinfunction "C3_5") (pintype "passive"))
      (node (ref "R27") (pin "2") (pinfunction "B_2") (pintype "passive"))
    )
    (net (code "54") (name "Net-(Q12D-B4)") (class "Default")
      (node (ref "Q12") (pin "9") (pinfunction "B4_9") (pintype "passive"))
      (node (ref "R30") (pin "2") (pinfunction "B_2") (pintype "passive"))
      (node (ref "R38") (pin "1") (pinfunction "A_1") (pintype "passive"))
    )
    (net (code "55") (name "Net-(Q12D-C4)") (class "Default")
      (node (ref "Q12") (pin "7") (pinfunction "C4_7") (pintype "passive"))
      (node (ref "R26") (pin "2") (pinfunction "B_2") (pintype "passive"))
    )
    (net (code "56") (name "Net-(R1-B)") (class "Default")
      (node (ref "Q1") (pin "G") (pinfunction "G_G") (pintype "passive"))
      (node (ref "R1") (pin "2") (pinfunction "B_2") (pintype "passive"))
      (node (ref "R2") (pin "1") (pinfunction "A_1") (pintype "passive"))
    )
    (net (code "57") (name "Net-(R2-B)") (class "Default")
      (node (ref "Q2") (pin "D") (pinfunction "D_D") (pintype "passive"))
      (node (ref "R2") (pin "2") (pinfunction "B_2") (pintype "passive"))
    )
    (net (code "58") (name "Net-(R3-A)") (class "Default")
      (node (ref "Q1") (pin "D") (pinfunction "D_D") (pintype "passive"))
      (node (ref "R3") (pin "1") (pinfunction "A_1") (pintype "passive"))
    )
    (net (code "59") (name "Net-(R14-A)") (class "Default")
      (node (ref "Q3") (pin "D") (pinfunction "D_D") (pintype "passive"))
      (node (ref "R14") (pin "1") (pinfunction "A_1") (pintype "passive"))
    )
    (net (code "60") (name "Net-(R15-A)") (class "Default")
      (node (ref "Q4") (pin "D") (pinfunction "D_D") (pintype "passive"))
      (node (ref "R15") (pin "1") (pinfunction "A_1") (pintype "passive"))
    )
    (net (code "61") (name "Net-(R16-A)") (class "Default")
      (node (ref "Q5") (pin "D") (pinfunction "D_D") (pintype "passive"))
      (node (ref "R16") (pin "1") (pinfunction "A_1") (pintype "passive"))
    )
    (net (code "62") (name "Net-(R17-A)") (class "Default")
      (node (ref "Q6") (pin "D") (pinfunction "D_D") (pintype "passive"))
      (node (ref "R17") (pin "1") (pinfunction "A_1") (pintype "passive"))
    )
    (net (code "63") (name "Net-(R22-B)") (class "Default")
      (node (ref "Q8") (pin "G") (pinfunction "G_G") (pintype "passive"))
      (node (ref "R22") (pin "2") (pinfunction "B_2") (pintype "passive"))
      (node (ref "R26") (pin "1") (pinfunction "A_1") (pintype "passive"))
    )
    (net (code "64") (name "Net-(R23-B)") (class "Default")
      (node (ref "Q9") (pin "G") (pinfunction "G_G") (pintype "passive"))
      (node (ref "R23") (pin "2") (pinfunction "B_2") (pintype "passive"))
      (node (ref "R27") (pin "1") (pinfunction "A_1") (pintype "passive"))
    )
    (net (code "65") (name "Net-(R24-B)") (class "Default")
      (node (ref "Q10") (pin "G") (pinfunction "G_G") (pintype "passive"))
      (node (ref "R24") (pin "2") (pinfunction "B_2") (pintype "passive"))
      (node (ref "R28") (pin "1") (pinfunction "A_1") (pintype "passive"))
    )
    (net (code "66") (name "Net-(R25-B)") (class "Default")
      (node (ref "Q11") (pin "G") (pinfunction "G_G") (pintype "passive"))
      (node (ref "R25") (pin "2") (pinfunction "B_2") (pintype "passive"))
      (node (ref "R29") (pin "1") (pinfunction "A_1") (pintype "passive"))
    )
    (net (code "67") (name "Net-(R34-A)") (class "Default")
      (node (ref "Q8") (pin "D") (pinfunction "D_D") (pintype "passive"))
      (node (ref "R34") (pin "1") (pinfunction "A_1") (pintype "passive"))
    )
    (net (code "68") (name "Net-(R35-A)") (class "Default")
      (node (ref "Q9") (pin "D") (pinfunction "D_D") (pintype "passive"))
      (node (ref "R35") (pin "1") (pinfunction "A_1") (pintype "passive"))
    )
    (net (code "69") (name "Net-(R36-A)") (class "Default")
      (node (ref "Q10") (pin "D") (pinfunction "D_D") (pintype "passive"))
      (node (ref "R36") (pin "1") (pinfunction "A_1") (pintype "passive"))
    )
    (net (code "70") (name "Net-(R37-A)") (class "Default")
      (node (ref "Q11") (pin "D") (pinfunction "D_D") (pintype "passive"))
      (node (ref "R37") (pin "1") (pinfunction "A_1") (pintype "passive"))
    )
    (net (code "71") (name "Net-(R42-B)") (class "Default")
      (node (ref "Q13") (pin "D") (pinfunction "D_D") (pintype "passive"))
      (node (ref "Q14") (pin "G") (pinfunction "G_G") (pintype "passive"))
      (node (ref "Q15") (pin "G") (pinfunction "G_G") (pintype "passive"))
      (node (ref "Q16") (pin "G") (pinfunction "G_G") (pintype "passive"))
      (node (ref "Q17") (pin "G") (pinfunction "G_G") (pintype "passive"))
      (node (ref "R42") (pin "2") (pinfunction "B_2") (pintype "passive"))
    )
    (net (code "72") (name "Net-(R43-A)") (class "Default")
      (node (ref "Q14") (pin "D") (pinfunction "D_D") (pintype "passive"))
      (node (ref "R43") (pin "1") (pinfunction "A_1") (pintype "passive"))
    )
    (net (code "73") (name "Net-(R44-A)") (class "Default")
      (node (ref "Q15") (pin "D") (pinfunction "D_D") (pintype "passive"))
      (node (ref "R44") (pin "1") (pinfunction "A_1") (pintype "passive"))
    )
    (net (code "74") (name "Net-(R45-A)") (class "Default")
      (node (ref "Q16") (pin "D") (pinfunction "D_D") (pintype "passive"))
      (node (ref "R45") (pin "1") (pinfunction "A_1") (pintype "passive"))
    )
    (net (code "75") (name "Net-(R46-A)") (class "Default")
      (node (ref "Q17") (pin "D") (pinfunction "D_D") (pintype "passive"))
      (node (ref "R46") (pin "1") (pinfunction "A_1") (pintype "passive"))
    )
    (net (code "76") (name "Net-(R51-B)") (class "Default")
      (node (ref "Q18") (pin "G") (pinfunction "G_G") (pintype "passive"))
      (node (ref "Q19") (pin "G") (pinfunction "G_G") (pintype "passive"))
      (node (ref "Q20") (pin "G") (pinfunction "G_G") (pintype "passive"))
      (node (ref "Q21") (pin "G") (pinfunction "G_G") (pintype "passive"))
      (node (ref "R51") (pin "2") (pinfunction "B_2") (pintype "passive"))
      (node (ref "R52") (pin "1") (pinfunction "A_1") (pintype "passive"))
    )
    (net (code "77") (name "Net-(R52-B)") (class "Default")
      (node (ref "Q22") (pin "D") (pinfunction "D_D") (pintype "passive"))
      (node (ref "R52") (pin "2") (pinfunction "B_2") (pintype "passive"))
    )
    (net (code "78") (name "Net-(R53-A)") (class "Default")
      (node (ref "Q18") (pin "D") (pinfunction "D_D") (pintype "passive"))
      (node (ref "R53") (pin "1") (pinfunction "A_1") (pintype "passive"))
    )
    (net (code "79") (name "Net-(R54-A)") (class "Default")
      (node (ref "Q19") (pin "D") (pinfunction "D_D") (pintype "passive"))
      (node (ref "R54") (pin "1") (pinfunction "A_1") (pintype "passive"))
    )
    (net (code "80") (name "Net-(R55-A)") (class "Default")
      (node (ref "Q20") (pin "D") (pinfunction "D_D") (pintype "passive"))
      (node (ref "R55") (pin "1") (pinfunction "A_1") (pintype "passive"))
    )
    (net (code "81") (name "Net-(R56-A)") (class "Default")
      (node (ref "Q21") (pin "D") (pinfunction "D_D") (pintype "passive"))
      (node (ref "R56") (pin "1") (pinfunction "A_1") (pintype "passive"))
    )
    (net (code "82") (name "unconnected-(U1-VZCR-Pad10)") (class "Default")
      (node (ref "U1") (pin "10") (pinfunction "VZCR_10") (pintype "output"))
    )
    (net (code "83") (name "unconnected-(U1-~{FAULT}-Pad13)") (class "Default")
      (node (ref "U1") (pin "13") (pinfunction "~{FAULT}_13") (pintype "output"))
    )
  )
)
